# Application_-_out8_16A_-_bistable_relay_.net
KiCad netlist of a schematic drawn in EAGLE
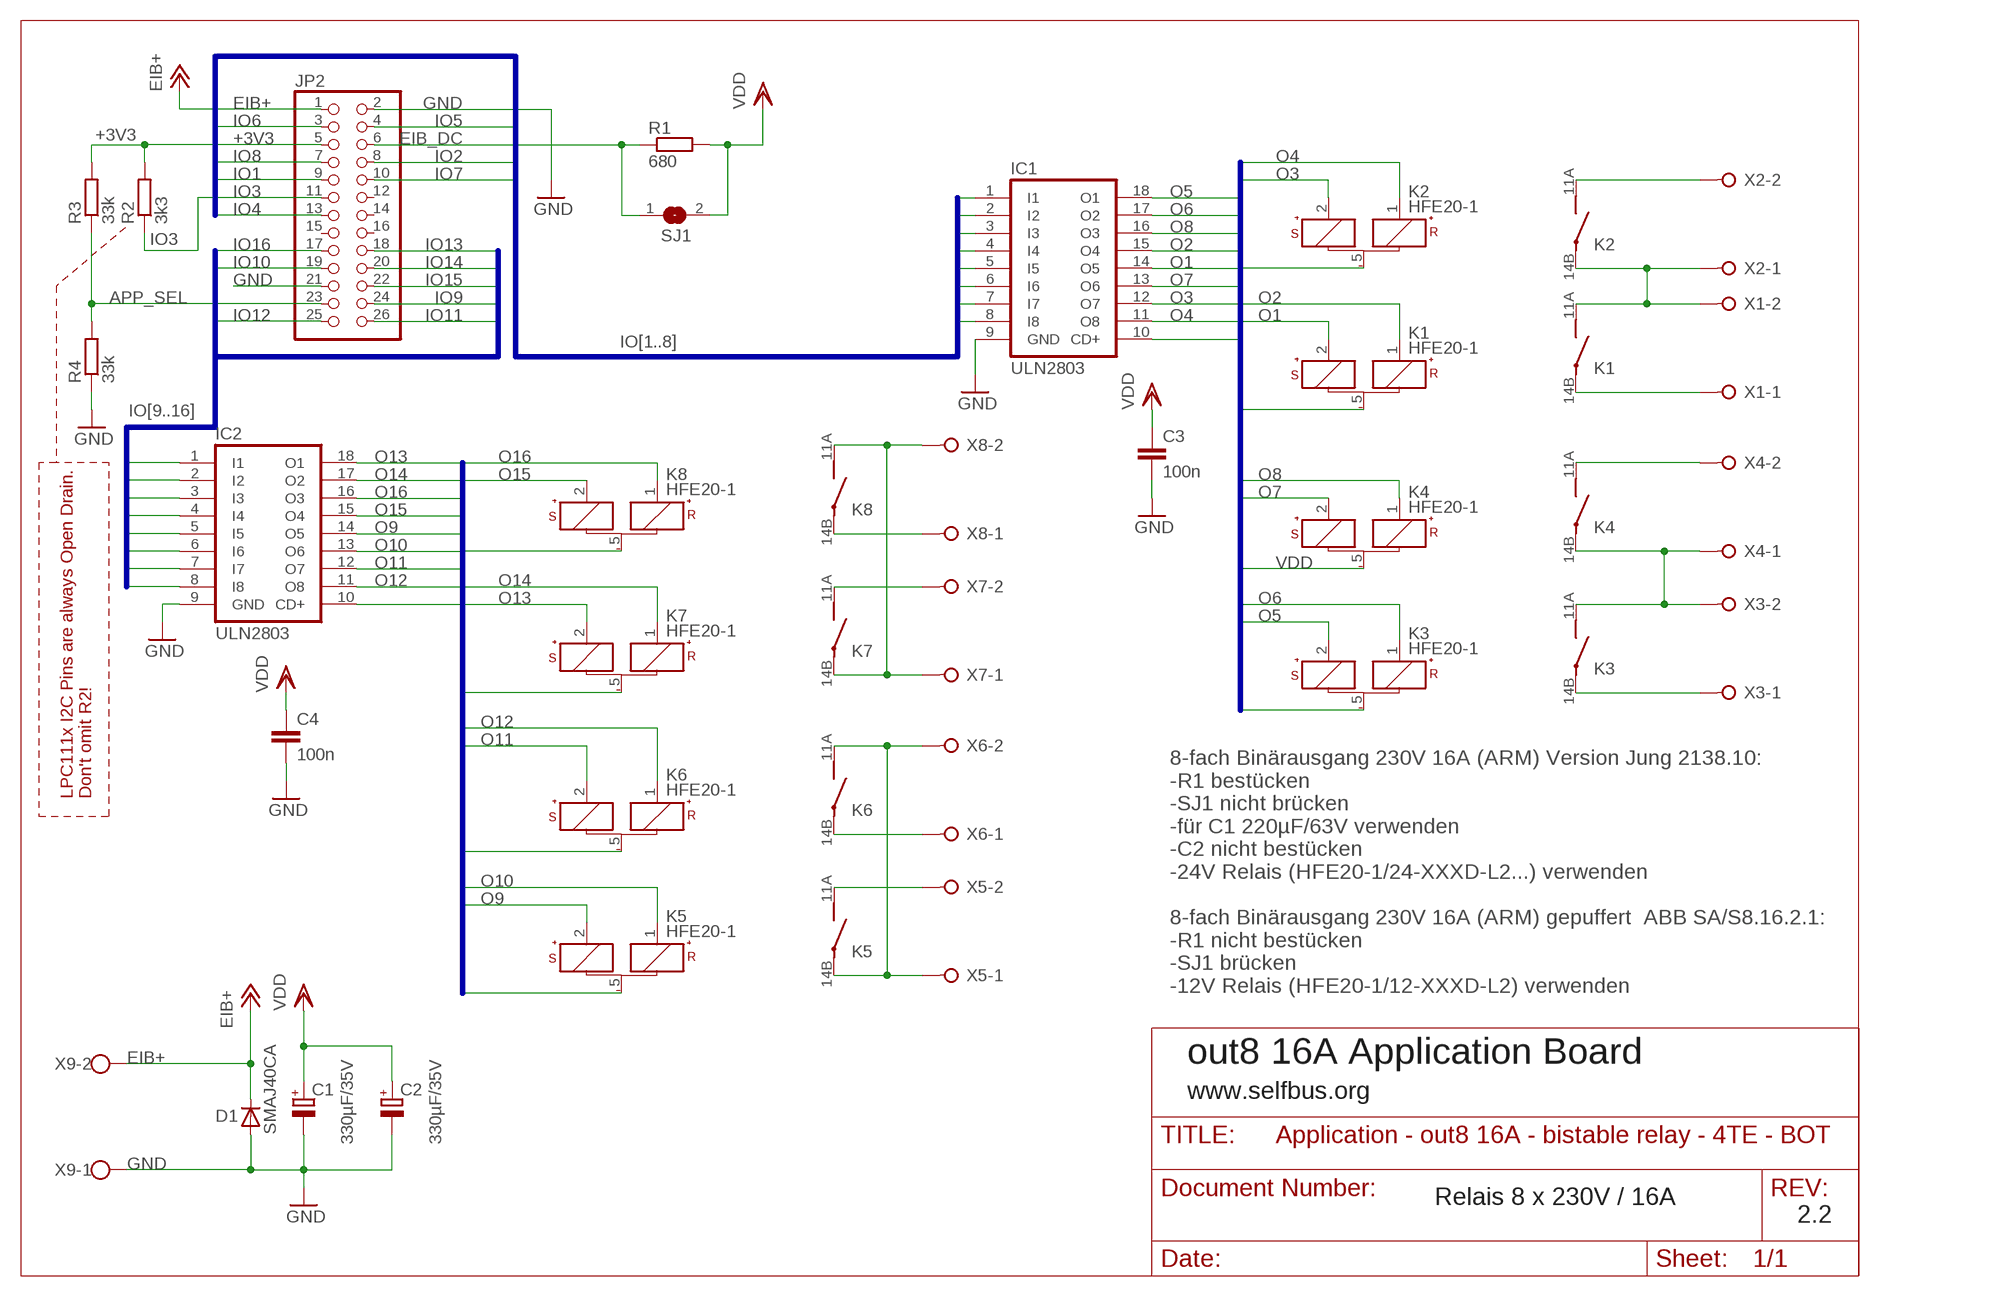
[diagram p0: schematic, sheet 1]

(export (version "E")
  (design (tool "Eeschema 10.0.6"))
  (components
    (comp (ref "C1")
      (value "330µF/35V")
      (footprint "eagle-import:E3,5-8")
      (libsource (lib "eagle-import") (part "CPOL-EUE3.5-8"))
    )
    (comp (ref "C2")
      (value "330µF/35V")
      (footprint "eagle-import:E3,5-8")
      (libsource (lib "eagle-import") (part "CPOL-EUE3.5-8"))
    )
    (comp (ref "C3")
      (value "100n")
      (footprint "eagle-import:C1206")
      (libsource (lib "eagle-import") (part "C-EUC1206"))
    )
    (comp (ref "C4")
      (value "100n")
      (footprint "eagle-import:C1206")
      (libsource (lib "eagle-import") (part "C-EUC1206"))
    )
    (comp (ref "D1")
      (value "SMAJ40CA")
      (footprint "eagle-import:SMB")
      (libsource (lib "eagle-import") (part "D-SMB"))
    )
    (comp (ref "IC1")
      (value "ULN2803")
      (footprint "eagle-import:SO18W")
      (libsource (lib "eagle-import") (part "ULN2803ASOP18"))
    )
    (comp (ref "IC2")
      (value "ULN2803")
      (footprint "eagle-import:SO18W")
      (libsource (lib "eagle-import") (part "ULN2803ASOP18"))
    )
    (comp (ref "JP2")
      (value "A")
      (footprint "eagle-import:2X13SMD")
      (libsource (lib "eagle-import") (part "PINHD-2X13_2.54-SMD"))
    )
    (comp (ref "K1")
      (value "HFE20-1")
      (footprint "eagle-import:HFE20-3-504")
      (libsource (lib "eagle-import") (part "HFE20-1-024-1HD504"))
    )
    (comp (ref "K2")
      (value "HFE20-1")
      (footprint "eagle-import:HFE20-3-504")
      (libsource (lib "eagle-import") (part "HFE20-1-024-1HD504"))
    )
    (comp (ref "K3")
      (value "HFE20-1")
      (footprint "eagle-import:HFE20-3-504")
      (libsource (lib "eagle-import") (part "HFE20-1-024-1HD504"))
    )
    (comp (ref "K4")
      (value "HFE20-1")
      (footprint "eagle-import:HFE20-3-504")
      (libsource (lib "eagle-import") (part "HFE20-1-024-1HD504"))
    )
    (comp (ref "K5")
      (value "HFE20-1")
      (footprint "eagle-import:HFE20-3-504")
      (libsource (lib "eagle-import") (part "HFE20-1-024-1HD504"))
    )
    (comp (ref "K6")
      (value "HFE20-1")
      (footprint "eagle-import:HFE20-3-504")
      (libsource (lib "eagle-import") (part "HFE20-1-024-1HD504"))
    )
    (comp (ref "K7")
      (value "HFE20-1")
      (footprint "eagle-import:HFE20-3-504")
      (libsource (lib "eagle-import") (part "HFE20-1-024-1HD504"))
    )
    (comp (ref "K8")
      (value "HFE20-1")
      (footprint "eagle-import:HFE20-3-504")
      (libsource (lib "eagle-import") (part "HFE20-1-024-1HD504"))
    )
    (comp (ref "R1")
      (value "680")
      (footprint "eagle-import:M1206")
      (libsource (lib "eagle-import") (part "R-EU_M1206"))
    )
    (comp (ref "R2")
      (value "3k3")
      (footprint "eagle-import:M1206")
      (libsource (lib "eagle-import") (part "R-EU_M1206"))
    )
    (comp (ref "R3")
      (value "33k")
      (footprint "eagle-import:M1206")
      (libsource (lib "eagle-import") (part "R-EU_M1206"))
    )
    (comp (ref "R4")
      (value "33k")
      (footprint "eagle-import:M1206")
      (libsource (lib "eagle-import") (part "R-EU_M1206"))
    )
    (comp (ref "SJ1") (value "A") (footprint "eagle-import:SJ") (libsource (lib "eagle-import") (part "SJ")))
    (comp (ref "X1")
      (value "W237-02P")
      (footprint "eagle-import:W237-132")
      (libsource (lib "eagle-import") (part "W237-02P"))
    )
    (comp (ref "X2")
      (value "W237-02P")
      (footprint "eagle-import:W237-132")
      (libsource (lib "eagle-import") (part "W237-02P"))
    )
    (comp (ref "X3")
      (value "W237-02P")
      (footprint "eagle-import:W237-132")
      (libsource (lib "eagle-import") (part "W237-02P"))
    )
    (comp (ref "X4")
      (value "W237-02P")
      (footprint "eagle-import:W237-132")
      (libsource (lib "eagle-import") (part "W237-02P"))
    )
    (comp (ref "X5")
      (value "W237-02P")
      (footprint "eagle-import:W237-132")
      (libsource (lib "eagle-import") (part "W237-02P"))
    )
    (comp (ref "X6")
      (value "W237-02P")
      (footprint "eagle-import:W237-132")
      (libsource (lib "eagle-import") (part "W237-02P"))
    )
    (comp (ref "X7")
      (value "W237-02P")
      (footprint "eagle-import:W237-132")
      (libsource (lib "eagle-import") (part "W237-02P"))
    )
    (comp (ref "X8")
      (value "W237-02P")
      (footprint "eagle-import:W237-132")
      (libsource (lib "eagle-import") (part "W237-02P"))
    )
    (comp (ref "X9")
      (value "W237-102")
      (footprint "eagle-import:W237-102")
      (libsource (lib "eagle-import") (part "W237-102"))
    )
  )
  (nets
    (net (code "1") (name "/+3V3") (class "Default")
      (node (ref "JP2") (pin "5") (pinfunction "5_5") (pintype "passive"))
      (node (ref "R2") (pin "2") (pinfunction "2_2") (pintype "passive"))
      (node (ref "R3") (pin "2") (pinfunction "2_2") (pintype "passive"))
    )
    (net (code "2") (name "/APP_SEL") (class "Default")
      (node (ref "JP2") (pin "23") (pinfunction "23_23") (pintype "passive"))
      (node (ref "R3") (pin "1") (pinfunction "1_1") (pintype "passive"))
      (node (ref "R4") (pin "2") (pinfunction "2_2") (pintype "passive"))
    )
    (net (code "3") (name "/EIB_DC") (class "Default")
      (node (ref "JP2") (pin "6") (pinfunction "6_6") (pintype "passive"))
      (node (ref "R1") (pin "1") (pinfunction "1_1") (pintype "passive"))
      (node (ref "SJ1") (pin "1") (pinfunction "1_1") (pintype "passive"))
    )
    (net (code "4") (name "/IO1") (class "Default")
      (node (ref "IC1") (pin "5") (pinfunction "I5_5") (pintype "input"))
      (node (ref "JP2") (pin "9") (pinfunction "9_9") (pintype "passive"))
    )
    (net (code "5") (name "/IO2") (class "Default")
      (node (ref "IC1") (pin "4") (pinfunction "I4_4") (pintype "input"))
      (node (ref "JP2") (pin "8") (pinfunction "8_8") (pintype "passive"))
    )
    (net (code "6") (name "/IO3") (class "Default")
      (node (ref "IC1") (pin "7") (pinfunction "I7_7") (pintype "input"))
      (node (ref "JP2") (pin "11") (pinfunction "11_11") (pintype "passive"))
      (node (ref "R2") (pin "1") (pinfunction "1_1") (pintype "passive"))
    )
    (net (code "7") (name "/IO4") (class "Default")
      (node (ref "IC1") (pin "8") (pinfunction "I8_8") (pintype "input"))
      (node (ref "JP2") (pin "13") (pinfunction "13_13") (pintype "passive"))
    )
    (net (code "8") (name "/IO5") (class "Default")
      (node (ref "IC1") (pin "1") (pinfunction "I1_1") (pintype "input"))
      (node (ref "JP2") (pin "4") (pinfunction "4_4") (pintype "passive"))
    )
    (net (code "9") (name "/IO6") (class "Default")
      (node (ref "IC1") (pin "2") (pinfunction "I2_2") (pintype "input"))
      (node (ref "JP2") (pin "3") (pinfunction "3_3") (pintype "passive"))
    )
    (net (code "10") (name "/IO7") (class "Default")
      (node (ref "IC1") (pin "6") (pinfunction "I6_6") (pintype "input"))
      (node (ref "JP2") (pin "10") (pinfunction "10_10") (pintype "passive"))
    )
    (net (code "11") (name "/IO8") (class "Default")
      (node (ref "IC1") (pin "3") (pinfunction "I3_3") (pintype "input"))
      (node (ref "JP2") (pin "7") (pinfunction "7_7") (pintype "passive"))
    )
    (net (code "12") (name "/IO9") (class "Default")
      (node (ref "IC2") (pin "5") (pinfunction "I5_5") (pintype "input"))
      (node (ref "JP2") (pin "24") (pinfunction "24_24") (pintype "passive"))
    )
    (net (code "13") (name "/IO10") (class "Default")
      (node (ref "IC2") (pin "6") (pinfunction "I6_6") (pintype "input"))
      (node (ref "JP2") (pin "19") (pinfunction "19_19") (pintype "passive"))
    )
    (net (code "14") (name "/IO11") (class "Default")
      (node (ref "IC2") (pin "7") (pinfunction "I7_7") (pintype "input"))
      (node (ref "JP2") (pin "26") (pinfunction "26_26") (pintype "passive"))
    )
    (net (code "15") (name "/IO12") (class "Default")
      (node (ref "IC2") (pin "8") (pinfunction "I8_8") (pintype "input"))
      (node (ref "JP2") (pin "25") (pinfunction "25_25") (pintype "passive"))
    )
    (net (code "16") (name "/IO13") (class "Default")
      (node (ref "IC2") (pin "1") (pinfunction "I1_1") (pintype "input"))
      (node (ref "JP2") (pin "18") (pinfunction "18_18") (pintype "passive"))
    )
    (net (code "17") (name "/IO14") (class "Default")
      (node (ref "IC2") (pin "2") (pinfunction "I2_2") (pintype "input"))
      (node (ref "JP2") (pin "20") (pinfunction "20_20") (pintype "passive"))
    )
    (net (code "18") (name "/IO15") (class "Default")
      (node (ref "IC2") (pin "4") (pinfunction "I4_4") (pintype "input"))
      (node (ref "JP2") (pin "22") (pinfunction "22_22") (pintype "passive"))
    )
    (net (code "19") (name "/IO16") (class "Default")
      (node (ref "IC2") (pin "3") (pinfunction "I3_3") (pintype "input"))
      (node (ref "JP2") (pin "17") (pinfunction "17_17") (pintype "passive"))
    )
    (net (code "22") (name "/O1") (class "Default")
      (node (ref "IC1") (pin "14") (pinfunction "O5_14") (pintype "open_collector"))
      (node (ref "K1") (pin "2") (pinfunction "S+_2") (pintype "passive"))
    )
    (net (code "23") (name "/O2") (class "Default")
      (node (ref "IC1") (pin "15") (pinfunction "O4_15") (pintype "open_collector"))
      (node (ref "K1") (pin "1") (pinfunction "R+_1") (pintype "passive"))
    )
    (net (code "24") (name "/O3") (class "Default")
      (node (ref "IC1") (pin "12") (pinfunction "O7_12") (pintype "open_collector"))
      (node (ref "K2") (pin "2") (pinfunction "S+_2") (pintype "passive"))
    )
    (net (code "25") (name "/O4") (class "Default")
      (node (ref "IC1") (pin "11") (pinfunction "O8_11") (pintype "open_collector"))
      (node (ref "K2") (pin "1") (pinfunction "R+_1") (pintype "passive"))
    )
    (net (code "26") (name "/O5") (class "Default")
      (node (ref "IC1") (pin "18") (pinfunction "O1_18") (pintype "open_collector"))
      (node (ref "K3") (pin "2") (pinfunction "S+_2") (pintype "passive"))
    )
    (net (code "27") (name "/O6") (class "Default")
      (node (ref "IC1") (pin "17") (pinfunction "O2_17") (pintype "open_collector"))
      (node (ref "K3") (pin "1") (pinfunction "R+_1") (pintype "passive"))
    )
    (net (code "28") (name "/O7") (class "Default")
      (node (ref "IC1") (pin "13") (pinfunction "O6_13") (pintype "open_collector"))
      (node (ref "K4") (pin "2") (pinfunction "S+_2") (pintype "passive"))
    )
    (net (code "29") (name "/O8") (class "Default")
      (node (ref "IC1") (pin "16") (pinfunction "O3_16") (pintype "open_collector"))
      (node (ref "K4") (pin "1") (pinfunction "R+_1") (pintype "passive"))
    )
    (net (code "30") (name "/O9") (class "Default")
      (node (ref "IC2") (pin "14") (pinfunction "O5_14") (pintype "open_collector"))
      (node (ref "K5") (pin "2") (pinfunction "S+_2") (pintype "passive"))
    )
    (net (code "31") (name "/O10") (class "Default")
      (node (ref "IC2") (pin "13") (pinfunction "O6_13") (pintype "open_collector"))
      (node (ref "K5") (pin "1") (pinfunction "R+_1") (pintype "passive"))
    )
    (net (code "32") (name "/O11") (class "Default")
      (node (ref "IC2") (pin "12") (pinfunction "O7_12") (pintype "open_collector"))
      (node (ref "K6") (pin "2") (pinfunction "S+_2") (pintype "passive"))
    )
    (net (code "33") (name "/O12") (class "Default")
      (node (ref "IC2") (pin "11") (pinfunction "O8_11") (pintype "open_collector"))
      (node (ref "K6") (pin "1") (pinfunction "R+_1") (pintype "passive"))
    )
    (net (code "34") (name "/O13") (class "Default")
      (node (ref "IC2") (pin "18") (pinfunction "O1_18") (pintype "open_collector"))
      (node (ref "K7") (pin "2") (pinfunction "S+_2") (pintype "passive"))
    )
    (net (code "35") (name "/O14") (class "Default")
      (node (ref "IC2") (pin "17") (pinfunction "O2_17") (pintype "open_collector"))
      (node (ref "K7") (pin "1") (pinfunction "R+_1") (pintype "passive"))
    )
    (net (code "36") (name "/O15") (class "Default")
      (node (ref "IC2") (pin "15") (pinfunction "O4_15") (pintype "open_collector"))
      (node (ref "K8") (pin "2") (pinfunction "S+_2") (pintype "passive"))
    )
    (net (code "37") (name "/O16") (class "Default")
      (node (ref "IC2") (pin "16") (pinfunction "O3_16") (pintype "open_collector"))
      (node (ref "K8") (pin "1") (pinfunction "R+_1") (pintype "passive"))
    )
    (net (code "38") (name "EIB+") (class "Default")
      (node (ref "D1") (pin "1") (pinfunction "C_1") (pintype "passive"))
      (node (ref "JP2") (pin "1") (pinfunction "1_1") (pintype "passive"))
      (node (ref "X9") (pin "2") (pinfunction "KL_2") (pintype "passive"))
    )
    (net (code "39") (name "GND") (class "Default")
      (node (ref "C1") (pin "-") (pinfunction "-_-") (pintype "passive"))
      (node (ref "C2") (pin "-") (pinfunction "-_-") (pintype "passive"))
      (node (ref "C3") (pin "2") (pinfunction "2_2") (pintype "passive"))
      (node (ref "C4") (pin "2") (pinfunction "2_2") (pintype "passive"))
      (node (ref "D1") (pin "2") (pinfunction "A_2") (pintype "passive"))
      (node (ref "IC1") (pin "9") (pinfunction "GND_9") (pintype "power_in"))
      (node (ref "IC2") (pin "9") (pinfunction "GND_9") (pintype "power_in"))
      (node (ref "JP2") (pin "2") (pinfunction "2_2") (pintype "passive"))
      (node (ref "JP2") (pin "21") (pinfunction "21_21") (pintype "passive"))
      (node (ref "R4") (pin "1") (pinfunction "1_1") (pintype "passive"))
      (node (ref "X9") (pin "1") (pinfunction "KL_1") (pintype "passive"))
    )
    (net (code "40") (name "Net-(K1B-PA)") (class "Default")
      (node (ref "K1") (pin "14B") (pinfunction "PA_14B") (pintype "passive"))
      (node (ref "X1") (pin "1") (pinfunction "KL_1") (pintype "passive"))
    )
    (net (code "41") (name "Net-(K1B-PB)") (class "Default")
      (node (ref "K1") (pin "11A") (pinfunction "PB_11A") (pintype "passive"))
      (node (ref "K2") (pin "14B") (pinfunction "PA_14B") (pintype "passive"))
      (node (ref "X1") (pin "2") (pinfunction "KL_2") (pintype "passive"))
      (node (ref "X2") (pin "1") (pinfunction "KL_1") (pintype "passive"))
    )
    (net (code "42") (name "Net-(K2B-PB)") (class "Default")
      (node (ref "K2") (pin "11A") (pinfunction "PB_11A") (pintype "passive"))
      (node (ref "X2") (pin "2") (pinfunction "KL_2") (pintype "passive"))
    )
    (net (code "43") (name "Net-(K3B-PA)") (class "Default")
      (node (ref "K3") (pin "14B") (pinfunction "PA_14B") (pintype "passive"))
      (node (ref "X3") (pin "1") (pinfunction "KL_1") (pintype "passive"))
    )
    (net (code "44") (name "Net-(K3B-PB)") (class "Default")
      (node (ref "K3") (pin "11A") (pinfunction "PB_11A") (pintype "passive"))
      (node (ref "K4") (pin "14B") (pinfunction "PA_14B") (pintype "passive"))
      (node (ref "X3") (pin "2") (pinfunction "KL_2") (pintype "passive"))
      (node (ref "X4") (pin "1") (pinfunction "KL_1") (pintype "passive"))
    )
    (net (code "45") (name "Net-(K4B-PB)") (class "Default")
      (node (ref "K4") (pin "11A") (pinfunction "PB_11A") (pintype "passive"))
      (node (ref "X4") (pin "2") (pinfunction "KL_2") (pintype "passive"))
    )
    (net (code "46") (name "Net-(K5B-PA)") (class "Default")
      (node (ref "K5") (pin "14B") (pinfunction "PA_14B") (pintype "passive"))
      (node (ref "K6") (pin "11A") (pinfunction "PB_11A") (pintype "passive"))
      (node (ref "X5") (pin "1") (pinfunction "KL_1") (pintype "passive"))
      (node (ref "X6") (pin "2") (pinfunction "KL_2") (pintype "passive"))
    )
    (net (code "47") (name "Net-(K5B-PB)") (class "Default")
      (node (ref "K5") (pin "11A") (pinfunction "PB_11A") (pintype "passive"))
      (node (ref "X5") (pin "2") (pinfunction "KL_2") (pintype "passive"))
    )
    (net (code "48") (name "Net-(K6B-PA)") (class "Default")
      (node (ref "K6") (pin "14B") (pinfunction "PA_14B") (pintype "passive"))
      (node (ref "X6") (pin "1") (pinfunction "KL_1") (pintype "passive"))
    )
    (net (code "49") (name "Net-(K7B-PA)") (class "Default")
      (node (ref "K7") (pin "14B") (pinfunction "PA_14B") (pintype "passive"))
      (node (ref "K8") (pin "11A") (pinfunction "PB_11A") (pintype "passive"))
      (node (ref "X7") (pin "1") (pinfunction "KL_1") (pintype "passive"))
      (node (ref "X8") (pin "2") (pinfunction "KL_2") (pintype "passive"))
    )
    (net (code "50") (name "Net-(K7B-PB)") (class "Default")
      (node (ref "K7") (pin "11A") (pinfunction "PB_11A") (pintype "passive"))
      (node (ref "X7") (pin "2") (pinfunction "KL_2") (pintype "passive"))
    )
    (net (code "51") (name "Net-(K8B-PA)") (class "Default")
      (node (ref "K8") (pin "14B") (pinfunction "PA_14B") (pintype "passive"))
      (node (ref "X8") (pin "1") (pinfunction "KL_1") (pintype "passive"))
    )
    (net (code "52") (name "VDD") (class "Default")
      (node (ref "C1") (pin "+") (pinfunction "+_+") (pintype "passive"))
      (node (ref "C2") (pin "+") (pinfunction "+_+") (pintype "passive"))
      (node (ref "C3") (pin "1") (pinfunction "1_1") (pintype "passive"))
      (node (ref "C4") (pin "1") (pinfunction "1_1") (pintype "passive"))
      (node (ref "IC1") (pin "10") (pinfunction "CD+_10") (pintype "passive"))
      (node (ref "IC2") (pin "10") (pinfunction "CD+_10") (pintype "passive"))
      (node (ref "K1") (pin "5") (pinfunction "-_5") (pintype "passive"))
      (node (ref "K2") (pin "5") (pinfunction "-_5") (pintype "passive"))
      (node (ref "K3") (pin "5") (pinfunction "-_5") (pintype "passive"))
      (node (ref "K4") (pin "5") (pinfunction "-_5") (pintype "passive"))
      (node (ref "K5") (pin "5") (pinfunction "-_5") (pintype "passive"))
      (node (ref "K6") (pin "5") (pinfunction "-_5") (pintype "passive"))
      (node (ref "K7") (pin "5") (pinfunction "-_5") (pintype "passive"))
      (node (ref "K8") (pin "5") (pinfunction "-_5") (pintype "passive"))
      (node (ref "R1") (pin "2") (pinfunction "2_2") (pintype "passive"))
      (node (ref "SJ1") (pin "2") (pinfunction "2_2") (pintype "passive"))
    )
    (net (code "53") (name "unconnected-(JP2-Pad12)") (class "Default")
      (node (ref "JP2") (pin "12") (pinfunction "12_12") (pintype "passive"))
    )
    (net (code "54") (name "unconnected-(JP2-Pad14)") (class "Default")
      (node (ref "JP2") (pin "14") (pinfunction "14_14") (pintype "passive"))
    )
    (net (code "55") (name "unconnected-(JP2-Pad15)") (class "Default")
      (node (ref "JP2") (pin "15") (pinfunction "15_15") (pintype "passive"))
    )
    (net (code "56") (name "unconnected-(JP2-Pad16)") (class "Default")
      (node (ref "JP2") (pin "16") (pinfunction "16_16") (pintype "passive"))
    )
  )
)
